# achizitie.net
KiCad netlist of a schematic drawn in EAGLE
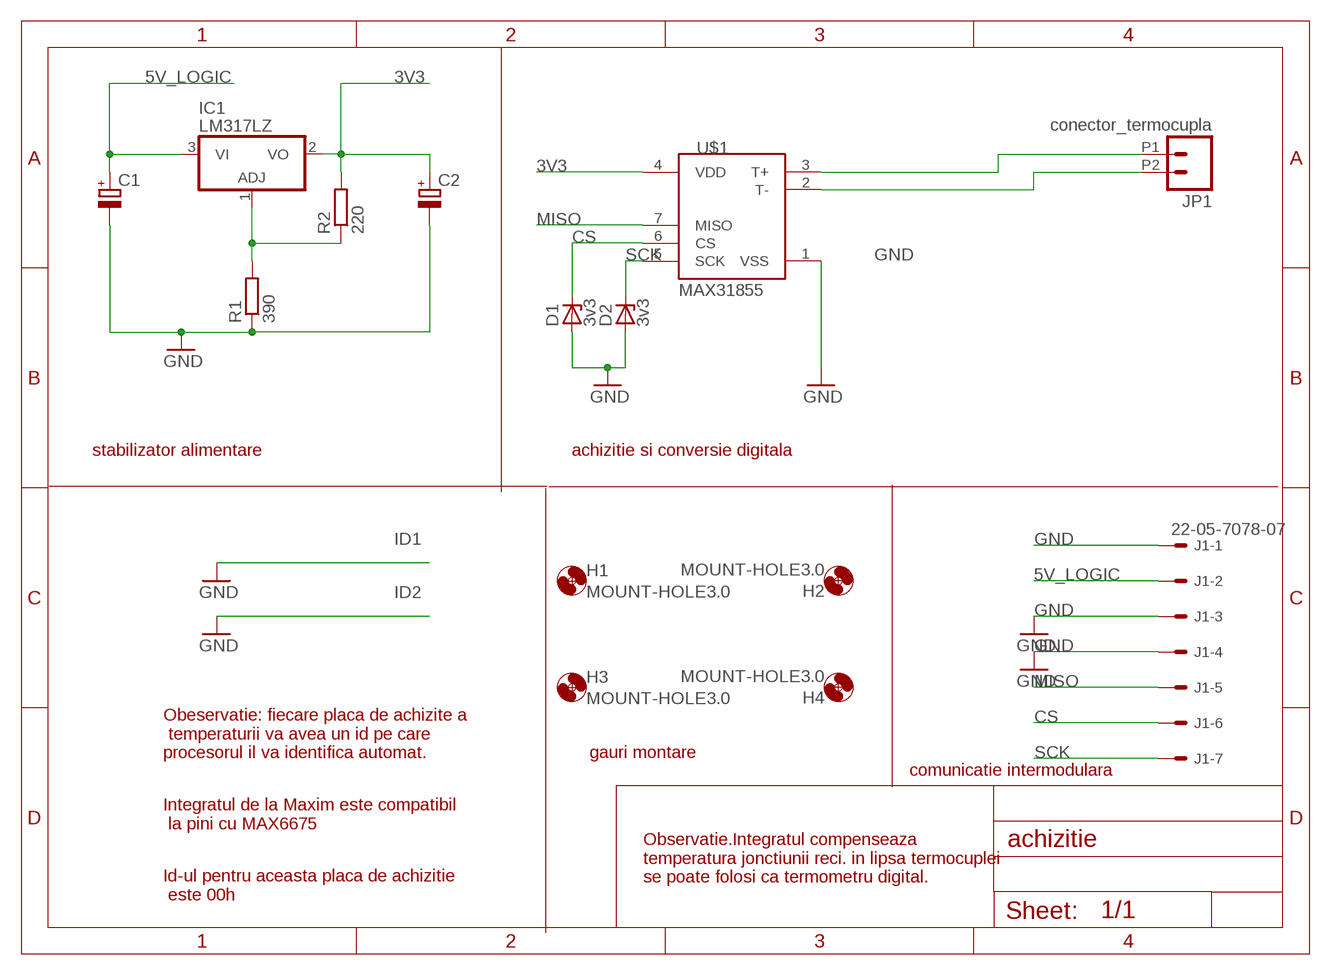
[diagram p0: schematic, sheet 1]

(export (version "E")
  (design (tool "Eeschema 10.0.6"))
  (components
    (comp (ref "C1")
      (value "CPOL-EUE2,5-6E")
      (footprint "eagle-import:E2,5-6E")
      (libsource (lib "eagle-import") (part "CPOL-EUE2,5-6E"))
    )
    (comp (ref "C2")
      (value "CPOL-EUE2,5-6E")
      (footprint "eagle-import:E2,5-6E")
      (libsource (lib "eagle-import") (part "CPOL-EUE2,5-6E"))
    )
    (comp (ref "D1")
      (value "3v3")
      (footprint "eagle-import:SOD80C")
      (libsource (lib "eagle-import") (part "ZENER-DIODESOD80C"))
    )
    (comp (ref "D2")
      (value "3v3")
      (footprint "eagle-import:SOD80C")
      (libsource (lib "eagle-import") (part "ZENER-DIODESOD80C"))
    )
    (comp (ref "H1")
      (value "MOUNT-HOLE3.0")
      (footprint "eagle-import:3,0")
      (libsource (lib "eagle-import") (part "MOUNT-HOLE3.0"))
    )
    (comp (ref "H2")
      (value "MOUNT-HOLE3.0")
      (footprint "eagle-import:3,0")
      (libsource (lib "eagle-import") (part "MOUNT-HOLE3.0"))
    )
    (comp (ref "H3")
      (value "MOUNT-HOLE3.0")
      (footprint "eagle-import:3,0")
      (libsource (lib "eagle-import") (part "MOUNT-HOLE3.0"))
    )
    (comp (ref "H4")
      (value "MOUNT-HOLE3.0")
      (footprint "eagle-import:3,0")
      (libsource (lib "eagle-import") (part "MOUNT-HOLE3.0"))
    )
    (comp (ref "IC1")
      (value "LM317LZ")
      (footprint "eagle-import:TO92")
      (libsource (lib "eagle-import") (part "317LZLM"))
    )
    (comp (ref "J1")
      (value "22-05-7078-07")
      (footprint "eagle-import:7395-07")
      (libsource (lib "eagle-import") (part "22-?-0705-7078"))
    )
    (comp (ref "JP1")
      (value "conector_termocupla")
      (footprint "eagle-import:1X02_2.54_SCREWTERM")
      (libsource (lib "eagle-import") (part "M022.54MM_SCREWTERM"))
    )
    (comp (ref "R1")
      (value "390")
      (footprint "eagle-import:M1206")
      (libsource (lib "eagle-import") (part "R-EU_M1206"))
    )
    (comp (ref "R2")
      (value "220")
      (footprint "eagle-import:M1206")
      (libsource (lib "eagle-import") (part "R-EU_M1206"))
    )
    (comp (ref "U$1")
      (value "MAX31855")
      (footprint "eagle-import:SO08-MAX6675")
      (libsource (lib "eagle-import") (part "MAX6675"))
    )
  )
  (nets
    (net (code "1") (name "/3V3") (class "Default")
      (node (ref "C2") (pin "+") (pinfunction "+_+") (pintype "passive"))
      (node (ref "IC1") (pin "2") (pinfunction "VO_2") (pintype "passive"))
      (node (ref "R2") (pin "2") (pinfunction "2_2") (pintype "passive"))
      (node (ref "U$1") (pin "4") (pinfunction "VDD_4") (pintype "bidirectional"))
    )
    (net (code "2") (name "/5V_LOGIC") (class "Default")
      (node (ref "C1") (pin "+") (pinfunction "+_+") (pintype "passive"))
      (node (ref "IC1") (pin "3") (pinfunction "VI_3") (pintype "input"))
      (node (ref "J1") (pin "2") (pinfunction "S_2") (pintype "passive"))
    )
    (net (code "3") (name "/CS") (class "Default")
      (node (ref "D1") (pin "C") (pinfunction "C_C") (pintype "passive"))
      (node (ref "J1") (pin "6") (pinfunction "S_6") (pintype "passive"))
      (node (ref "U$1") (pin "6") (pinfunction "CS_6") (pintype "bidirectional"))
    )
    (net (code "4") (name "/MISO") (class "Default")
      (node (ref "J1") (pin "5") (pinfunction "S_5") (pintype "passive"))
      (node (ref "U$1") (pin "7") (pinfunction "MISO_7") (pintype "bidirectional"))
    )
    (net (code "5") (name "/SCK") (class "Default")
      (node (ref "D2") (pin "C") (pinfunction "C_C") (pintype "passive"))
      (node (ref "J1") (pin "7") (pinfunction "S_7") (pintype "passive"))
      (node (ref "U$1") (pin "5") (pinfunction "SCK_5") (pintype "bidirectional"))
    )
    (net (code "6") (name "GND") (class "Default")
      (node (ref "C1") (pin "-") (pinfunction "-_-") (pintype "passive"))
      (node (ref "C2") (pin "-") (pinfunction "-_-") (pintype "passive"))
      (node (ref "D1") (pin "A") (pinfunction "A_A") (pintype "passive"))
      (node (ref "D2") (pin "A") (pinfunction "A_A") (pintype "passive"))
      (node (ref "J1") (pin "1") (pinfunction "S_1") (pintype "passive"))
      (node (ref "J1") (pin "3") (pinfunction "S_3") (pintype "passive"))
      (node (ref "J1") (pin "4") (pinfunction "S_4") (pintype "passive"))
      (node (ref "R1") (pin "1") (pinfunction "1_1") (pintype "passive"))
      (node (ref "U$1") (pin "1") (pinfunction "VSS_1") (pintype "bidirectional"))
    )
    (net (code "7") (name "Net-(IC1-ADJ)") (class "Default")
      (node (ref "IC1") (pin "1") (pinfunction "ADJ_1") (pintype "input"))
      (node (ref "R1") (pin "2") (pinfunction "2_2") (pintype "passive"))
      (node (ref "R2") (pin "1") (pinfunction "1_1") (pintype "passive"))
    )
    (net (code "8") (name "Net-(JP1-1)") (class "Default")
      (node (ref "JP1") (pin "P1") (pinfunction "1_P1") (pintype "passive"))
      (node (ref "U$1") (pin "3") (pinfunction "T+_3") (pintype "bidirectional"))
    )
    (net (code "9") (name "Net-(JP1-2)") (class "Default")
      (node (ref "JP1") (pin "P2") (pinfunction "2_P2") (pintype "passive"))
      (node (ref "U$1") (pin "2") (pinfunction "T-_2") (pintype "bidirectional"))
    )
  )
)
